# self_leveling_tray_schematic.net
KiCad netlist of a schematic drawn in EAGLE
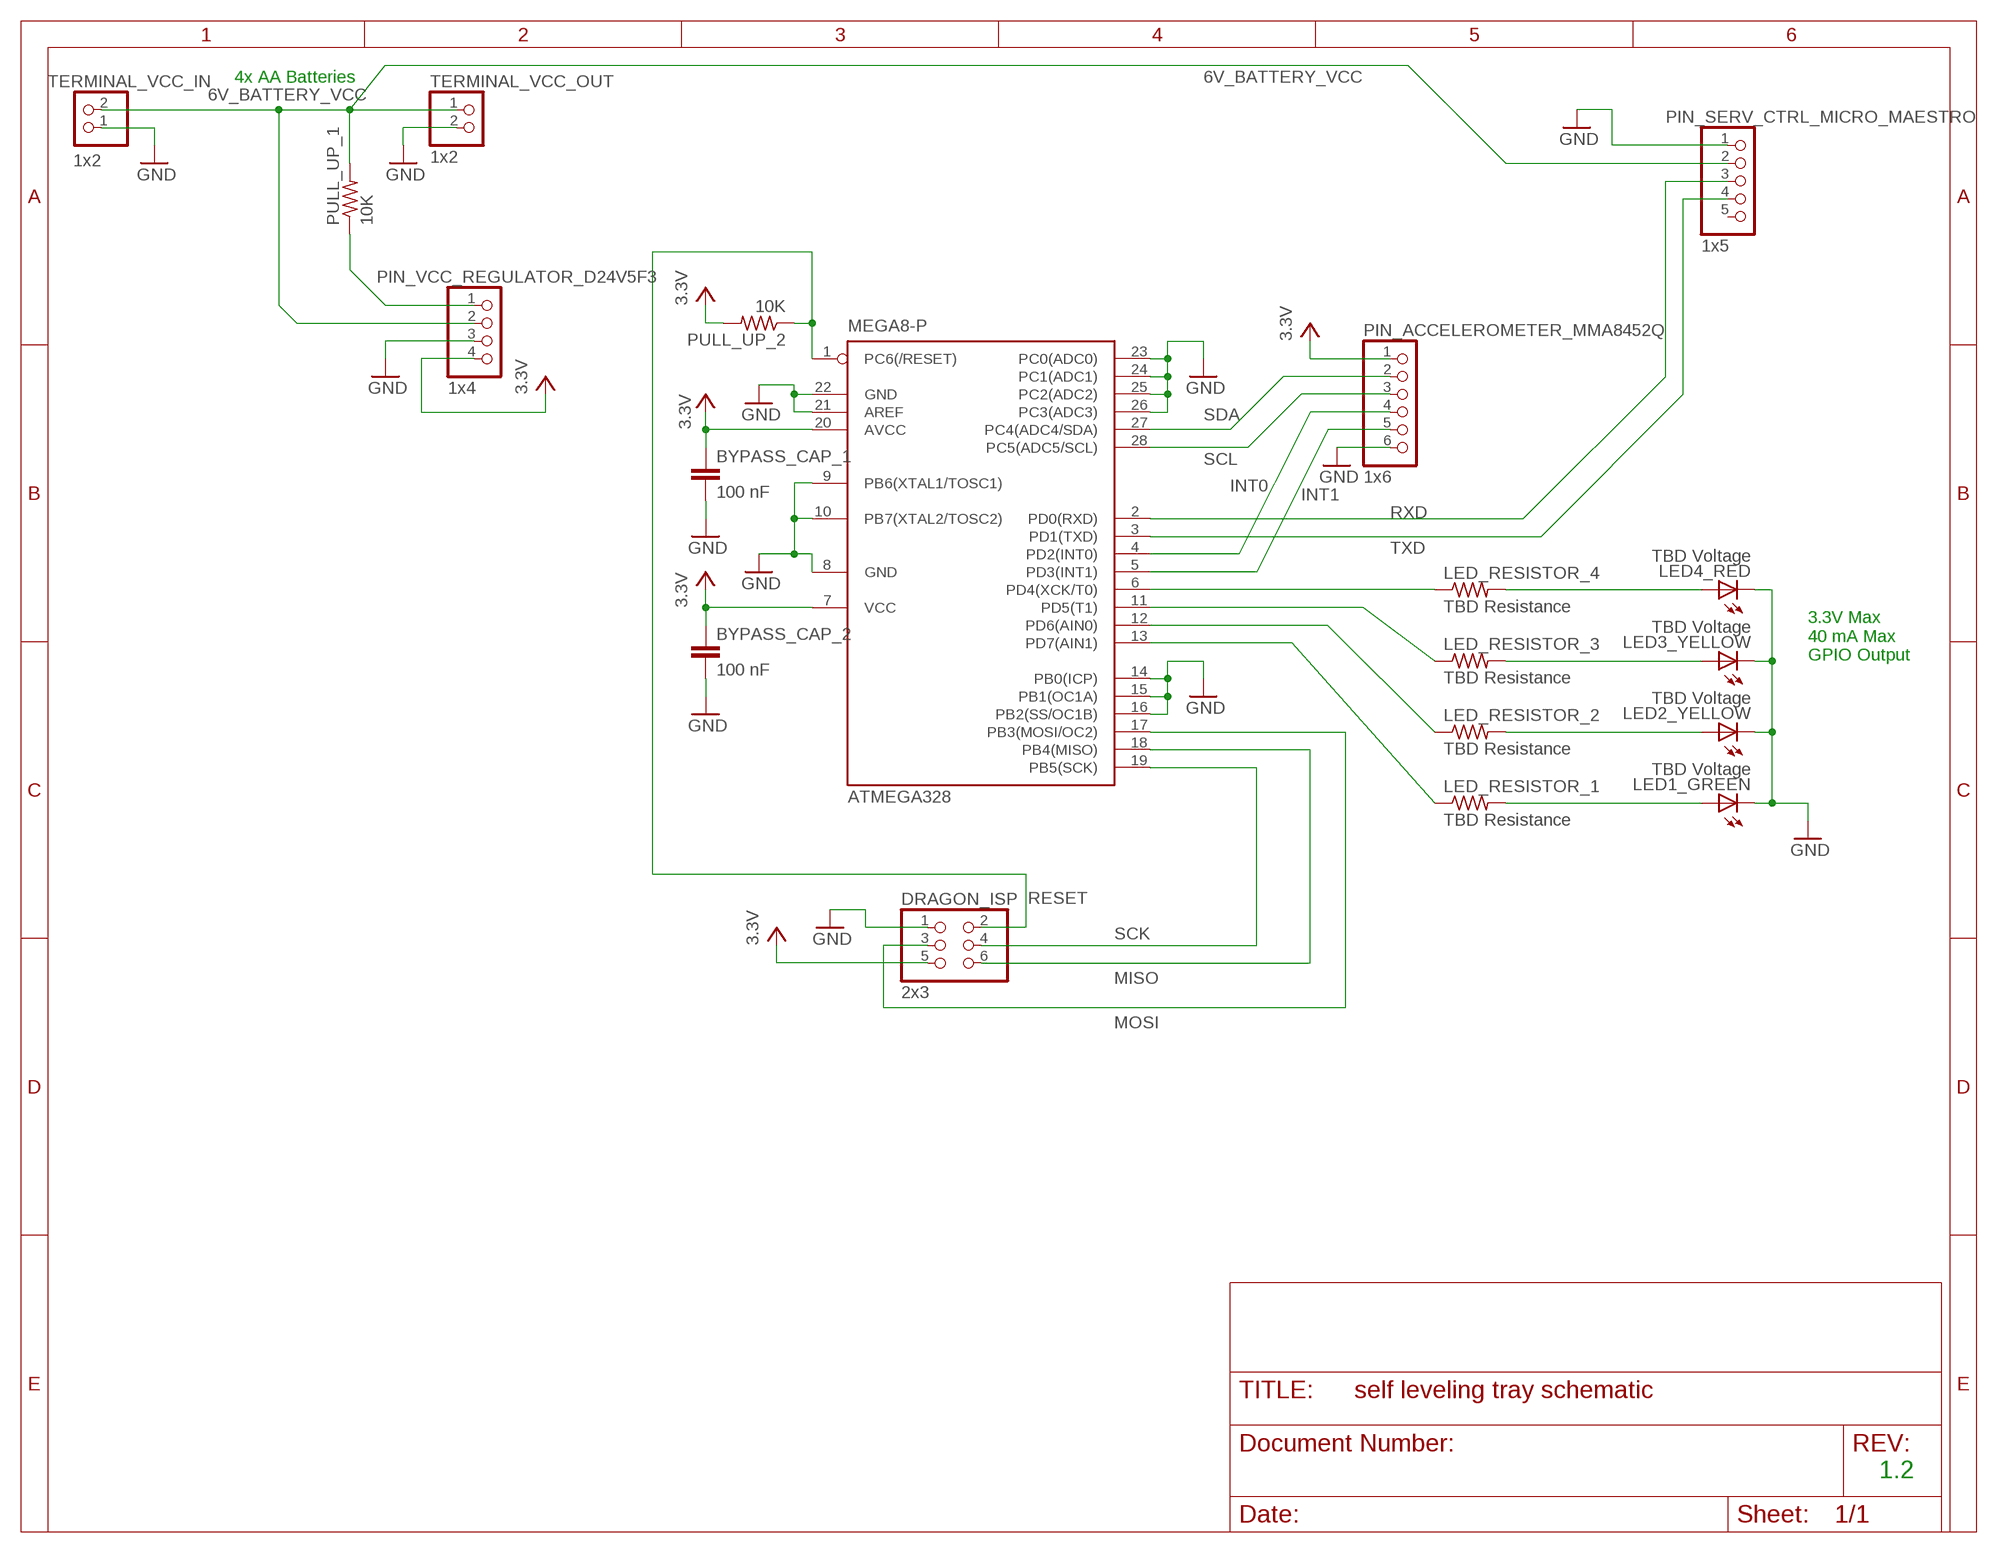
[diagram p0: schematic, sheet 1]

(export (version "E")
  (design (tool "Eeschema 10.0.6"))
  (components
    (comp (ref "ATMEGA328")
      (value "MEGA8-P")
      (footprint "eagle-import:DIL28-3")
      (libsource (lib "eagle-import") (part "MEGA8-P"))
    )
    (comp (ref "BYPASS_CAP_1")
      (value "100 nF")
      (footprint "eagle-import:C1206")
      (libsource (lib "eagle-import") (part "C-EUC1206"))
    )
    (comp (ref "BYPASS_CAP_2")
      (value "100 nF")
      (footprint "eagle-import:C1206")
      (libsource (lib "eagle-import") (part "C-EUC1206"))
    )
    (comp (ref "DRAGON_ISP")
      (value "2x3")
      (footprint "eagle-import:2X03")
      (libsource (lib "eagle-import") (part "PINHD-2X3"))
    )
    (comp (ref "LED1_GREEN")
      (value "TBD Voltage")
      (footprint "eagle-import:1206")
      (libsource (lib "eagle-import") (part "LEDSMT1206"))
    )
    (comp (ref "LED2_YELLOW")
      (value "TBD Voltage")
      (footprint "eagle-import:1206")
      (libsource (lib "eagle-import") (part "LEDSMT1206"))
    )
    (comp (ref "LED3_YELLOW")
      (value "TBD Voltage")
      (footprint "eagle-import:1206")
      (libsource (lib "eagle-import") (part "LEDSMT1206"))
    )
    (comp (ref "LED4_RED")
      (value "TBD Voltage")
      (footprint "eagle-import:1206")
      (libsource (lib "eagle-import") (part "LEDSMT1206"))
    )
    (comp (ref "LED_RESISTOR_1")
      (value "TBD Resistance")
      (footprint "eagle-import:R1206")
      (libsource (lib "eagle-import") (part "R-US_R1206"))
    )
    (comp (ref "LED_RESISTOR_2")
      (value "TBD Resistance")
      (footprint "eagle-import:R1206")
      (libsource (lib "eagle-import") (part "R-US_R1206"))
    )
    (comp (ref "LED_RESISTOR_3")
      (value "TBD Resistance")
      (footprint "eagle-import:R1206")
      (libsource (lib "eagle-import") (part "R-US_R1206"))
    )
    (comp (ref "LED_RESISTOR_4")
      (value "TBD Resistance")
      (footprint "eagle-import:R1206")
      (libsource (lib "eagle-import") (part "R-US_R1206"))
    )
    (comp (ref "PIN_ACCELEROMETER_MMA8452Q")
      (value "1x6")
      (footprint "eagle-import:1X06")
      (libsource (lib "eagle-import") (part "PINHD-1X6"))
    )
    (comp (ref "PIN_SERV_CTRL_MICRO_MAESTRO")
      (value "1x5")
      (footprint "eagle-import:1X05")
      (libsource (lib "eagle-import") (part "PINHD-1X5"))
    )
    (comp (ref "PIN_VCC_REGULATOR_D24V5F3")
      (value "1x4")
      (footprint "eagle-import:1X04")
      (libsource (lib "eagle-import") (part "PINHD-1X4"))
    )
    (comp (ref "PULL_UP_1")
      (value "10K")
      (footprint "eagle-import:M1206")
      (libsource (lib "eagle-import") (part "R-US_M1206"))
    )
    (comp (ref "PULL_UP_2")
      (value "10K")
      (footprint "eagle-import:M1206")
      (libsource (lib "eagle-import") (part "R-US_M1206"))
    )
    (comp (ref "TERMINAL_VCC_IN")
      (value "1x2")
      (footprint "eagle-import:1X02")
      (libsource (lib "eagle-import") (part "PINHD-1X2"))
    )
    (comp (ref "TERMINAL_VCC_OUT")
      (value "1x2")
      (footprint "eagle-import:1X02")
      (libsource (lib "eagle-import") (part "PINHD-1X2"))
    )
  )
  (nets
    (net (code "1") (name "/6V_BATTERY_VCC") (class "Default")
      (node (ref "PIN_SERV_CTRL_MICRO_MAESTRO") (pin "2") (pinfunction "2_2") (pintype "passive"))
      (node (ref "PIN_VCC_REGULATOR_D24V5F3") (pin "2") (pinfunction "2_2") (pintype "passive"))
      (node (ref "PULL_UP_1") (pin "2") (pinfunction "2_2") (pintype "passive"))
      (node (ref "TERMINAL_VCC_IN") (pin "2") (pinfunction "2_2") (pintype "passive"))
      (node (ref "TERMINAL_VCC_OUT") (pin "1") (pinfunction "1_1") (pintype "passive"))
    )
    (net (code "2") (name "/INT0") (class "Default")
      (node (ref "ATMEGA328") (pin "4") (pinfunction "PD2(INT0)_4") (pintype "bidirectional"))
      (node (ref "PIN_ACCELEROMETER_MMA8452Q") (pin "4") (pinfunction "4_4") (pintype "passive"))
    )
    (net (code "3") (name "/INT1") (class "Default")
      (node (ref "ATMEGA328") (pin "5") (pinfunction "PD3(INT1)_5") (pintype "bidirectional"))
      (node (ref "PIN_ACCELEROMETER_MMA8452Q") (pin "5") (pinfunction "5_5") (pintype "passive"))
    )
    (net (code "4") (name "/MISO") (class "Default")
      (node (ref "ATMEGA328") (pin "18") (pinfunction "PB4(MISO)_18") (pintype "bidirectional"))
      (node (ref "DRAGON_ISP") (pin "6") (pinfunction "6_6") (pintype "passive"))
    )
    (net (code "5") (name "/MOSI") (class "Default")
      (node (ref "ATMEGA328") (pin "17") (pinfunction "PB3(MOSI/OC2)_17") (pintype "bidirectional"))
      (node (ref "DRAGON_ISP") (pin "3") (pinfunction "3_3") (pintype "passive"))
    )
    (net (code "6") (name "/RESET") (class "Default")
      (node (ref "ATMEGA328") (pin "1") (pinfunction "PC6(/RESET)_1") (pintype "bidirectional"))
      (node (ref "DRAGON_ISP") (pin "2") (pinfunction "2_2") (pintype "passive"))
      (node (ref "PULL_UP_2") (pin "1") (pinfunction "1_1") (pintype "passive"))
    )
    (net (code "7") (name "/RXD") (class "Default")
      (node (ref "ATMEGA328") (pin "2") (pinfunction "PD0(RXD)_2") (pintype "bidirectional"))
      (node (ref "PIN_SERV_CTRL_MICRO_MAESTRO") (pin "3") (pinfunction "3_3") (pintype "passive"))
    )
    (net (code "8") (name "/SCK") (class "Default")
      (node (ref "ATMEGA328") (pin "19") (pinfunction "PB5(SCK)_19") (pintype "bidirectional"))
      (node (ref "DRAGON_ISP") (pin "4") (pinfunction "4_4") (pintype "passive"))
    )
    (net (code "9") (name "/SCL") (class "Default")
      (node (ref "ATMEGA328") (pin "28") (pinfunction "PC5(ADC5/SCL)_28") (pintype "bidirectional"))
      (node (ref "PIN_ACCELEROMETER_MMA8452Q") (pin "3") (pinfunction "3_3") (pintype "passive"))
    )
    (net (code "10") (name "/SDA") (class "Default")
      (node (ref "ATMEGA328") (pin "27") (pinfunction "PC4(ADC4/SDA)_27") (pintype "bidirectional"))
      (node (ref "PIN_ACCELEROMETER_MMA8452Q") (pin "2") (pinfunction "2_2") (pintype "passive"))
    )
    (net (code "11") (name "/TXD") (class "Default")
      (node (ref "ATMEGA328") (pin "3") (pinfunction "PD1(TXD)_3") (pintype "bidirectional"))
      (node (ref "PIN_SERV_CTRL_MICRO_MAESTRO") (pin "4") (pinfunction "4_4") (pintype "passive"))
    )
    (net (code "12") (name "3.3V") (class "Default")
      (node (ref "ATMEGA328") (pin "20") (pinfunction "AVCC_20") (pintype "power_in"))
      (node (ref "ATMEGA328") (pin "7") (pinfunction "VCC_7") (pintype "power_in"))
      (node (ref "BYPASS_CAP_1") (pin "1") (pinfunction "1_1") (pintype "passive"))
      (node (ref "BYPASS_CAP_2") (pin "1") (pinfunction "1_1") (pintype "passive"))
      (node (ref "DRAGON_ISP") (pin "5") (pinfunction "5_5") (pintype "passive"))
      (node (ref "PIN_ACCELEROMETER_MMA8452Q") (pin "1") (pinfunction "1_1") (pintype "passive"))
      (node (ref "PIN_VCC_REGULATOR_D24V5F3") (pin "4") (pinfunction "4_4") (pintype "passive"))
      (node (ref "PULL_UP_2") (pin "2") (pinfunction "2_2") (pintype "passive"))
    )
    (net (code "13") (name "GND") (class "Default")
      (node (ref "ATMEGA328") (pin "10") (pinfunction "PB7(XTAL2/TOSC2)_10") (pintype "bidirectional"))
      (node (ref "ATMEGA328") (pin "14") (pinfunction "PB0(ICP)_14") (pintype "bidirectional"))
      (node (ref "ATMEGA328") (pin "15") (pinfunction "PB1(OC1A)_15") (pintype "bidirectional"))
      (node (ref "ATMEGA328") (pin "16") (pinfunction "PB2(SS/OC1B)_16") (pintype "bidirectional"))
      (node (ref "ATMEGA328") (pin "21") (pinfunction "AREF_21") (pintype "passive"))
      (node (ref "ATMEGA328") (pin "22") (pinfunction "GND_22") (pintype "power_in"))
      (node (ref "ATMEGA328") (pin "23") (pinfunction "PC0(ADC0)_23") (pintype "bidirectional"))
      (node (ref "ATMEGA328") (pin "24") (pinfunction "PC1(ADC1)_24") (pintype "bidirectional"))
      (node (ref "ATMEGA328") (pin "25") (pinfunction "PC2(ADC2)_25") (pintype "bidirectional"))
      (node (ref "ATMEGA328") (pin "26") (pinfunction "PC3(ADC3)_26") (pintype "bidirectional"))
      (node (ref "ATMEGA328") (pin "8") (pinfunction "GND_8") (pintype "power_in"))
      (node (ref "ATMEGA328") (pin "9") (pinfunction "PB6(XTAL1/TOSC1)_9") (pintype "bidirectional"))
      (node (ref "BYPASS_CAP_1") (pin "2") (pinfunction "2_2") (pintype "passive"))
      (node (ref "BYPASS_CAP_2") (pin "2") (pinfunction "2_2") (pintype "passive"))
      (node (ref "DRAGON_ISP") (pin "1") (pinfunction "1_1") (pintype "passive"))
      (node (ref "LED1_GREEN") (pin "C") (pinfunction "C_C") (pintype "passive"))
      (node (ref "LED2_YELLOW") (pin "C") (pinfunction "C_C") (pintype "passive"))
      (node (ref "LED3_YELLOW") (pin "C") (pinfunction "C_C") (pintype "passive"))
      (node (ref "LED4_RED") (pin "C") (pinfunction "C_C") (pintype "passive"))
      (node (ref "PIN_ACCELEROMETER_MMA8452Q") (pin "6") (pinfunction "6_6") (pintype "passive"))
      (node (ref "PIN_SERV_CTRL_MICRO_MAESTRO") (pin "1") (pinfunction "1_1") (pintype "passive"))
      (node (ref "PIN_VCC_REGULATOR_D24V5F3") (pin "3") (pinfunction "3_3") (pintype "passive"))
      (node (ref "TERMINAL_VCC_IN") (pin "1") (pinfunction "1_1") (pintype "passive"))
      (node (ref "TERMINAL_VCC_OUT") (pin "2") (pinfunction "2_2") (pintype "passive"))
    )
    (net (code "14") (name "Net-(ATMEGA328-PD4(XCK{slash}T0))") (class "Default")
      (node (ref "ATMEGA328") (pin "6") (pinfunction "PD4(XCK/T0)_6") (pintype "bidirectional"))
      (node (ref "LED_RESISTOR_4") (pin "1") (pinfunction "1_1") (pintype "passive"))
    )
    (net (code "15") (name "Net-(ATMEGA328-PD5(T1))") (class "Default")
      (node (ref "ATMEGA328") (pin "11") (pinfunction "PD5(T1)_11") (pintype "bidirectional"))
      (node (ref "LED_RESISTOR_3") (pin "1") (pinfunction "1_1") (pintype "passive"))
    )
    (net (code "16") (name "Net-(ATMEGA328-PD6(AIN0))") (class "Default")
      (node (ref "ATMEGA328") (pin "12") (pinfunction "PD6(AIN0)_12") (pintype "bidirectional"))
      (node (ref "LED_RESISTOR_2") (pin "1") (pinfunction "1_1") (pintype "passive"))
    )
    (net (code "17") (name "Net-(ATMEGA328-PD7(AIN1))") (class "Default")
      (node (ref "ATMEGA328") (pin "13") (pinfunction "PD7(AIN1)_13") (pintype "bidirectional"))
      (node (ref "LED_RESISTOR_1") (pin "1") (pinfunction "1_1") (pintype "passive"))
    )
    (net (code "18") (name "Net-(LED1_GREEN-PadA)") (class "Default")
      (node (ref "LED1_GREEN") (pin "A") (pinfunction "A_A") (pintype "passive"))
      (node (ref "LED_RESISTOR_1") (pin "2") (pinfunction "2_2") (pintype "passive"))
    )
    (net (code "19") (name "Net-(LED2_YELLOW-PadA)") (class "Default")
      (node (ref "LED2_YELLOW") (pin "A") (pinfunction "A_A") (pintype "passive"))
      (node (ref "LED_RESISTOR_2") (pin "2") (pinfunction "2_2") (pintype "passive"))
    )
    (net (code "20") (name "Net-(LED3_YELLOW-PadA)") (class "Default")
      (node (ref "LED3_YELLOW") (pin "A") (pinfunction "A_A") (pintype "passive"))
      (node (ref "LED_RESISTOR_3") (pin "2") (pinfunction "2_2") (pintype "passive"))
    )
    (net (code "21") (name "Net-(LED4_RED-PadA)") (class "Default")
      (node (ref "LED4_RED") (pin "A") (pinfunction "A_A") (pintype "passive"))
      (node (ref "LED_RESISTOR_4") (pin "2") (pinfunction "2_2") (pintype "passive"))
    )
    (net (code "22") (name "Net-(PIN_VCC_REGULATOR_D24V5F3-Pad1)") (class "Default")
      (node (ref "PIN_VCC_REGULATOR_D24V5F3") (pin "1") (pinfunction "1_1") (pintype "passive"))
      (node (ref "PULL_UP_1") (pin "1") (pinfunction "1_1") (pintype "passive"))
    )
    (net (code "23") (name "unconnected-(PIN_SERV_CTRL_MICRO_MAESTRO-Pad5)") (class "Default")
      (node (ref "PIN_SERV_CTRL_MICRO_MAESTRO") (pin "5") (pinfunction "5_5") (pintype "passive"))
    )
  )
)
